# Adafruit_PowerBoost_500C.net
KiCad netlist of a schematic drawn in EAGLE
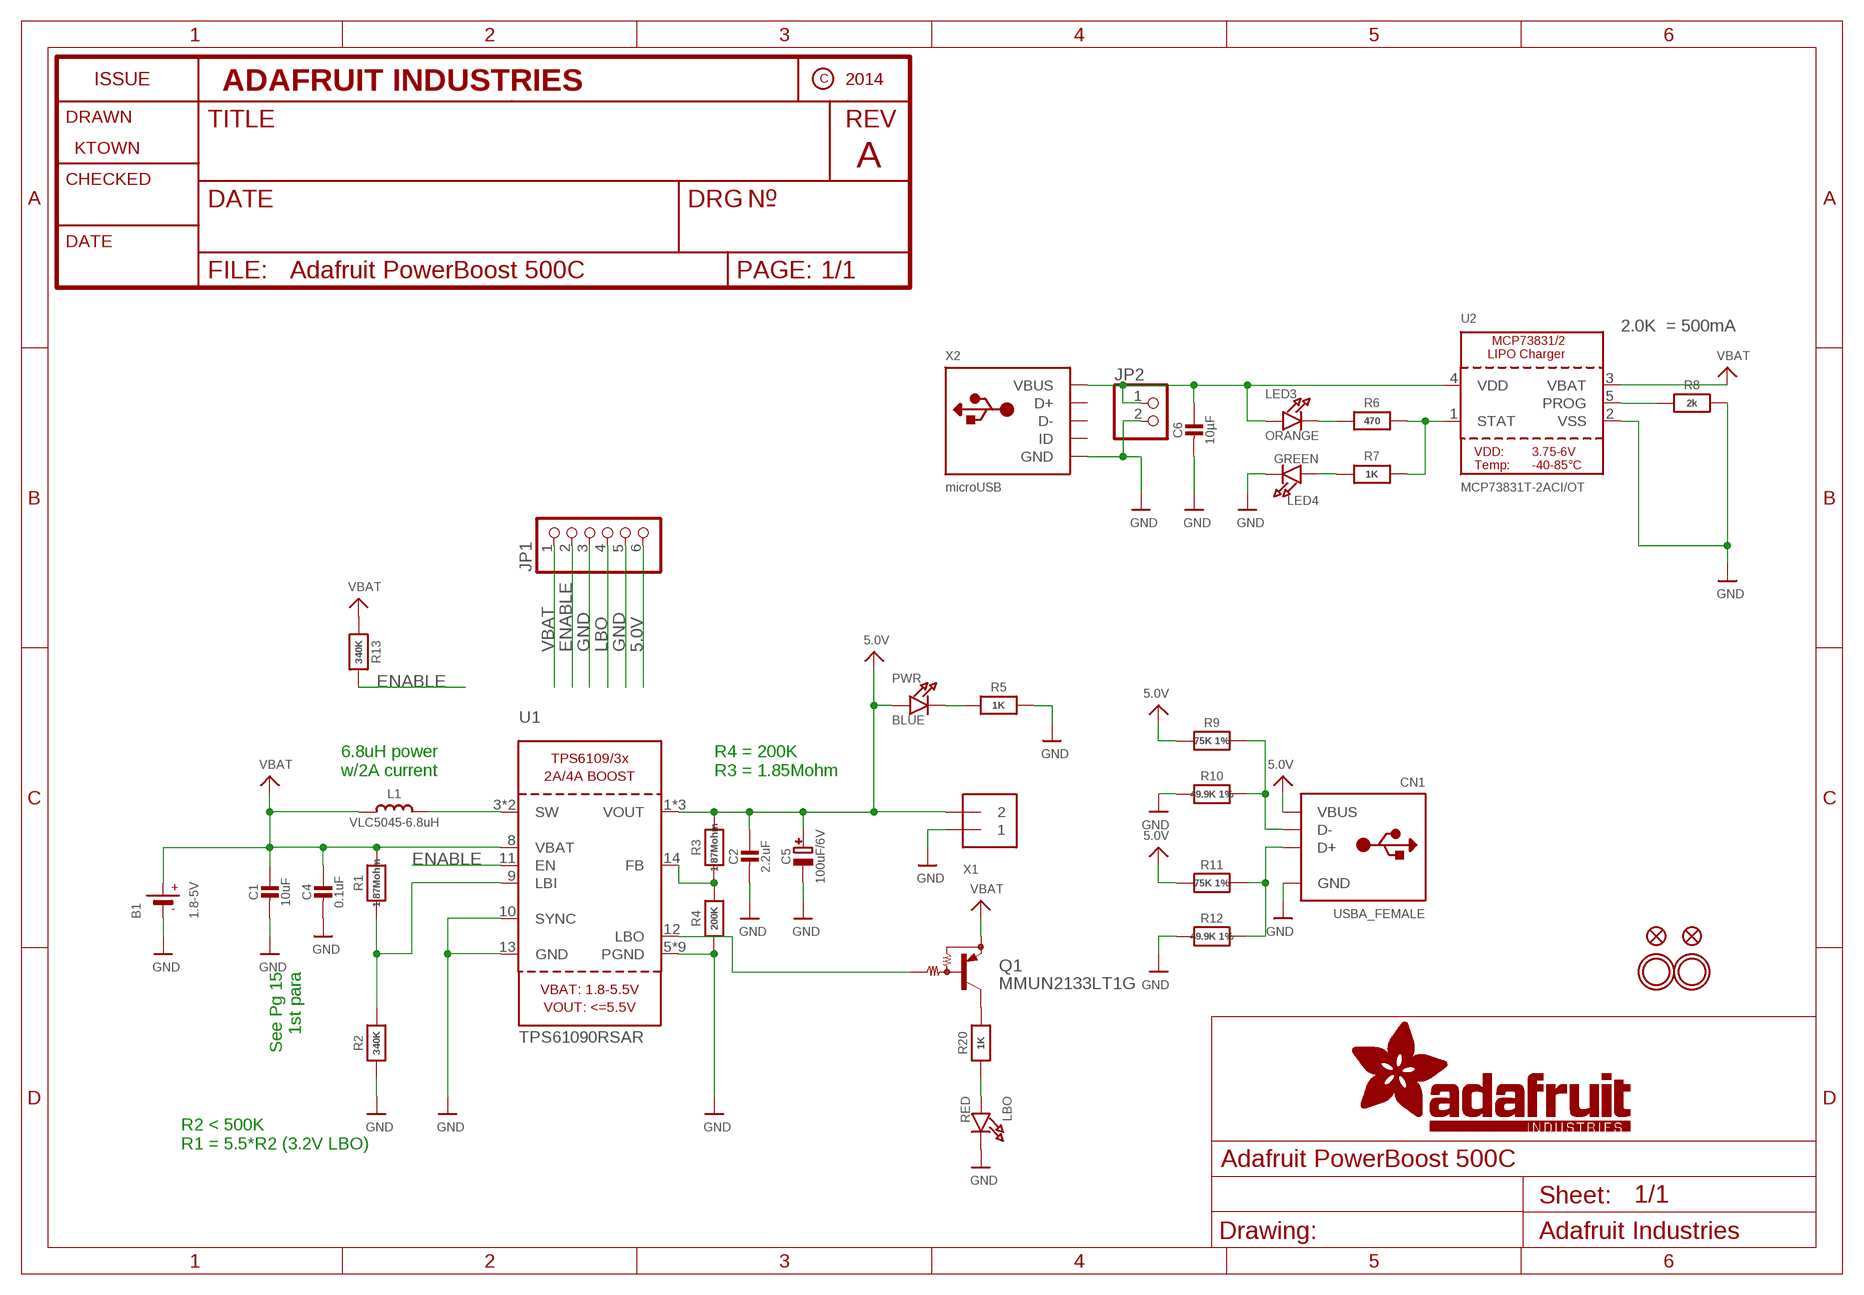
[diagram p0: schematic, sheet 1]

(export (version "E")
  (design (tool "Eeschema 10.0.6"))
  (components
    (comp (ref "B1")
      (value "1.8-5V")
      (footprint "eagle-import:JSTPH2")
      (libsource (lib "eagle-import") (part "BATTERY"))
    )
    (comp (ref "C1")
      (value "10uF")
      (footprint "eagle-import:0805-NO")
      (libsource (lib "eagle-import") (part "CAP_CERAMIC0805-NOOUTLINE"))
    )
    (comp (ref "C2")
      (value "2.2uF")
      (footprint "eagle-import:0805-NO")
      (libsource (lib "eagle-import") (part "CAP_CERAMIC0805-NOOUTLINE"))
    )
    (comp (ref "C4")
      (value "0.1uF")
      (footprint "eagle-import:0805-NO")
      (libsource (lib "eagle-import") (part "CAP_CERAMIC0805-NOOUTLINE"))
    )
    (comp (ref "C5")
      (value "100uF/6V")
      (footprint "eagle-import:EIA3528-21_B-R")
      (libsource (lib "eagle-import") (part "CAP_TANTALUMB/3528_REFLOW"))
    )
    (comp (ref "C6")
      (value "10µF")
      (footprint "eagle-import:0805-NO")
      (libsource (lib "eagle-import") (part "CAP_CERAMIC0805-NOOUTLINE"))
    )
    (comp (ref "CN1")
      (value "USBA_FEMALE")
      (footprint "eagle-import:USB_HOST-PTH")
      (libsource (lib "eagle-import") (part "USB_TYPEAPTHFML"))
    )
    (comp (ref "FID2")
      (value "FIDUCIAL\"\"")
      (footprint "eagle-import:FIDUCIAL_1MM")
      (libsource (lib "eagle-import") (part "FIDUCIAL{dblquote}{dblquote}"))
    )
    (comp (ref "FID3")
      (value "FIDUCIAL\"\"")
      (footprint "eagle-import:FIDUCIAL_1MM")
      (fields (field (name "BOM") "EXCLUDE"))
      (libsource (lib "eagle-import") (part "FIDUCIAL{dblquote}{dblquote}"))
    )
    (comp (ref "JP1")
      (value "PINHD-1X6CB")
      (footprint "eagle-import:1X06-CLEANBIG")
      (libsource (lib "eagle-import") (part "PINHD-1X6CB"))
    )
    (comp (ref "JP2")
      (value "HEADER-1X2ROUND")
      (footprint "eagle-import:1X02_ROUND")
      (libsource (lib "eagle-import") (part "HEADER-1X2ROUND"))
    )
    (comp (ref "L1")
      (value "VLC5045-6.8uH")
      (footprint "eagle-import:INDUCTOR_5X5MM_TDK_VLC5045")
      (libsource (lib "eagle-import") (part "INDUCTORTDK_VLC5045"))
    )
    (comp (ref "LBO")
      (value "RED")
      (footprint "eagle-import:CHIPLED_0805_NOOUTLINE")
      (libsource (lib "eagle-import") (part "LED0805_NOOUTLINE"))
    )
    (comp (ref "LED3")
      (value "ORANGE")
      (footprint "eagle-import:CHIPLED_0805_NOOUTLINE")
      (libsource (lib "eagle-import") (part "LED0805_NOOUTLINE"))
    )
    (comp (ref "LED4")
      (value "GREEN")
      (footprint "eagle-import:CHIPLED_0805_NOOUTLINE")
      (libsource (lib "eagle-import") (part "LED0805_NOOUTLINE"))
    )
    (comp (ref "PWR")
      (value "BLUE")
      (footprint "eagle-import:CHIPLED_0805_NOOUTLINE")
      (libsource (lib "eagle-import") (part "LED0805_NOOUTLINE"))
    )
    (comp (ref "Q1")
      (value "MMUN2133LT1G")
      (footprint "eagle-import:SC59-BEC")
      (libsource (lib "eagle-import") (part "-PNP_DRIVER-SC59-BECMUN2114T1"))
    )
    (comp (ref "R1")
      (value "1.87Mohm")
      (footprint "eagle-import:0805-NO")
      (libsource (lib "eagle-import") (part "RESISTOR0805_NOOUTLINE"))
    )
    (comp (ref "R2")
      (value "340K")
      (footprint "eagle-import:0805-NO")
      (libsource (lib "eagle-import") (part "RESISTOR0805_NOOUTLINE"))
    )
    (comp (ref "R3")
      (value "1.87Mohm")
      (footprint "eagle-import:0805-NO")
      (libsource (lib "eagle-import") (part "RESISTOR0805_NOOUTLINE"))
    )
    (comp (ref "R4")
      (value "200K")
      (footprint "eagle-import:0805-NO")
      (libsource (lib "eagle-import") (part "RESISTOR0805_NOOUTLINE"))
    )
    (comp (ref "R5")
      (value "1K")
      (footprint "eagle-import:0805-NO")
      (libsource (lib "eagle-import") (part "RESISTOR0805_NOOUTLINE"))
    )
    (comp (ref "R6")
      (value "470")
      (footprint "eagle-import:0805-NO")
      (libsource (lib "eagle-import") (part "RESISTOR0805_NOOUTLINE"))
    )
    (comp (ref "R7")
      (value "1K")
      (footprint "eagle-import:0805-NO")
      (libsource (lib "eagle-import") (part "RESISTOR0805_NOOUTLINE"))
    )
    (comp (ref "R8")
      (value "2k")
      (footprint "eagle-import:0805-NO")
      (libsource (lib "eagle-import") (part "RESISTOR0805_NOOUTLINE"))
    )
    (comp (ref "R9")
      (value "75K 1%")
      (footprint "eagle-import:0805-NO")
      (libsource (lib "eagle-import") (part "RESISTOR0805_NOOUTLINE"))
    )
    (comp (ref "R10")
      (value "49.9K 1%")
      (footprint "eagle-import:0805-NO")
      (libsource (lib "eagle-import") (part "RESISTOR0805_NOOUTLINE"))
    )
    (comp (ref "R11")
      (value "75K 1%")
      (footprint "eagle-import:0805-NO")
      (libsource (lib "eagle-import") (part "RESISTOR0805_NOOUTLINE"))
    )
    (comp (ref "R12")
      (value "49.9K 1%")
      (footprint "eagle-import:0805-NO")
      (libsource (lib "eagle-import") (part "RESISTOR0805_NOOUTLINE"))
    )
    (comp (ref "R13")
      (value "340K")
      (footprint "eagle-import:0805-NO")
      (libsource (lib "eagle-import") (part "RESISTOR0805_NOOUTLINE"))
    )
    (comp (ref "R20")
      (value "1K")
      (footprint "eagle-import:0805-NO")
      (libsource (lib "eagle-import") (part "RESISTOR0805_NOOUTLINE"))
    )
    (comp (ref "U$10")
      (value "MOUNTINGHOLE2.5")
      (footprint "eagle-import:MOUNTINGHOLE_2.5_PLATED")
      (libsource (lib "eagle-import") (part "MOUNTINGHOLE2.5"))
    )
    (comp (ref "U$12")
      (value "MOUNTINGHOLE2.5")
      (footprint "eagle-import:MOUNTINGHOLE_2.5_PLATED")
      (libsource (lib "eagle-import") (part "MOUNTINGHOLE2.5"))
    )
    (comp (ref "U1")
      (value "TPS61090RSAR")
      (footprint "eagle-import:PVQFN-16")
      (libsource (lib "eagle-import") (part "VREG_TPS6103X"))
    )
    (comp (ref "U2")
      (value "MCP73831T-2ACI/OT")
      (footprint "eagle-import:SOT23-5")
      (libsource (lib "eagle-import") (part "MCP73831/2"))
    )
    (comp (ref "X1")
      (value "TERMBLOCK_1X2")
      (footprint "eagle-import:TERMBLOCK_1X2-3.5MM")
      (libsource (lib "eagle-import") (part "TERMBLOCK_1X2"))
    )
    (comp (ref "X2")
      (value "microUSB")
      (footprint "eagle-import:4UCONN_20329")
      (libsource (lib "eagle-import") (part "USBMICRO_20329"))
    )
  )
  (nets
    (net (code "1") (name "/ENABLE") (class "Default")
      (node (ref "JP1") (pin "2") (pinfunction "2_2") (pintype "passive"))
      (node (ref "R13") (pin "2") (pinfunction "2_2") (pintype "passive"))
      (node (ref "U1") (pin "11") (pinfunction "EN_11") (pintype "input"))
    )
    (net (code "2") (name "/LBO") (class "Default")
      (node (ref "JP1") (pin "4") (pinfunction "4_4") (pintype "passive"))
      (node (ref "Q1") (pin "B") (pinfunction "B_B") (pintype "passive"))
      (node (ref "U1") (pin "12") (pinfunction "LBO_12") (pintype "output"))
    )
    (net (code "3") (name "5.0V") (class "Default")
      (node (ref "C2") (pin "1") (pinfunction "1_1") (pintype "passive"))
      (node (ref "C5") (pin "+") (pinfunction "+_+") (pintype "passive"))
      (node (ref "CN1") (pin "VBUS") (pinfunction "VBUS_VBUS") (pintype "power_in"))
      (node (ref "JP1") (pin "6") (pinfunction "6_6") (pintype "passive"))
      (node (ref "PWR") (pin "A") (pinfunction "A_A") (pintype "passive"))
      (node (ref "R11") (pin "2") (pinfunction "2_2") (pintype "passive"))
      (node (ref "R3") (pin "2") (pinfunction "2_2") (pintype "passive"))
      (node (ref "R9") (pin "2") (pinfunction "2_2") (pintype "passive"))
      (node (ref "U1") (pin "1") (pinfunction "VOUT_1") (pintype "power_in"))
      (node (ref "U1") (pin "15") (pinfunction "VOUT_15") (pintype "power_in"))
      (node (ref "U1") (pin "16") (pinfunction "VOUT_16") (pintype "power_in"))
      (node (ref "X1") (pin "2") (pinfunction "2_2") (pintype "passive"))
    )
    (net (code "4") (name "GND") (class "Default")
      (node (ref "B1") (pin "1") (pinfunction "-_1") (pintype "passive"))
      (node (ref "C1") (pin "2") (pinfunction "2_2") (pintype "passive"))
      (node (ref "C2") (pin "2") (pinfunction "2_2") (pintype "passive"))
      (node (ref "C4") (pin "2") (pinfunction "2_2") (pintype "passive"))
      (node (ref "C5") (pin "-") (pinfunction "-_-") (pintype "passive"))
      (node (ref "C6") (pin "2") (pinfunction "2_2") (pintype "passive"))
      (node (ref "CN1") (pin "GND") (pinfunction "GND_GND") (pintype "power_in"))
      (node (ref "JP1") (pin "3") (pinfunction "3_3") (pintype "passive"))
      (node (ref "JP1") (pin "5") (pinfunction "5_5") (pintype "passive"))
      (node (ref "JP2") (pin "2") (pinfunction "2_2") (pintype "passive"))
      (node (ref "LBO") (pin "C") (pinfunction "C_C") (pintype "passive"))
      (node (ref "LED4") (pin "C") (pinfunction "C_C") (pintype "passive"))
      (node (ref "R10") (pin "2") (pinfunction "2_2") (pintype "passive"))
      (node (ref "R12") (pin "2") (pinfunction "2_2") (pintype "passive"))
      (node (ref "R2") (pin "1") (pinfunction "1_1") (pintype "passive"))
      (node (ref "R4") (pin "1") (pinfunction "1_1") (pintype "passive"))
      (node (ref "R5") (pin "2") (pinfunction "2_2") (pintype "passive"))
      (node (ref "R8") (pin "2") (pinfunction "2_2") (pintype "passive"))
      (node (ref "U1") (pin "10") (pinfunction "SYNC_10") (pintype "input"))
      (node (ref "U1") (pin "13") (pinfunction "GND_13") (pintype "power_in"))
      (node (ref "U1") (pin "5") (pinfunction "PGND_5") (pintype "power_in"))
      (node (ref "U1") (pin "6") (pinfunction "PGND_6") (pintype "power_in"))
      (node (ref "U1") (pin "7") (pinfunction "PGND_7") (pintype "power_in"))
      (node (ref "U1") (pin "P$18") (pinfunction "PGND_P$18") (pintype "power_in"))
      (node (ref "U1") (pin "P$19") (pinfunction "PGND_P$19") (pintype "power_in"))
      (node (ref "U1") (pin "P$20") (pinfunction "PGND_P$20") (pintype "power_in"))
      (node (ref "U1") (pin "P$21") (pinfunction "PGND_P$21") (pintype "power_in"))
      (node (ref "U1") (pin "P$22") (pinfunction "PGND_P$22") (pintype "power_in"))
      (node (ref "U1") (pin "THERMAL") (pinfunction "PGND_THERMAL") (pintype "power_in"))
      (node (ref "U2") (pin "2") (pinfunction "VSS_2") (pintype "power_in"))
      (node (ref "X1") (pin "1") (pinfunction "1_1") (pintype "passive"))
      (node (ref "X2") (pin "BASE@1") (pinfunction "GND_BASE@1") (pintype "power_in"))
      (node (ref "X2") (pin "BASE@2") (pinfunction "GND_BASE@2") (pintype "power_in"))
      (node (ref "X2") (pin "GND") (pinfunction "GND_GND") (pintype "power_in"))
      (node (ref "X2") (pin "SPRT@1") (pinfunction "GND_SPRT@1") (pintype "power_in"))
      (node (ref "X2") (pin "SPRT@2") (pinfunction "GND_SPRT@2") (pintype "power_in"))
      (node (ref "X2") (pin "SPRT@3") (pinfunction "GND_SPRT@3") (pintype "power_in"))
      (node (ref "X2") (pin "SPRT@4") (pinfunction "GND_SPRT@4") (pintype "power_in"))
    )
    (net (code "5") (name "Net-(CN1-PadD+)") (class "Default")
      (node (ref "CN1") (pin "D+") (pinfunction "D+_D+") (pintype "bidirectional"))
      (node (ref "R11") (pin "1") (pinfunction "1_1") (pintype "passive"))
      (node (ref "R12") (pin "1") (pinfunction "1_1") (pintype "passive"))
    )
    (net (code "6") (name "Net-(CN1-PadD-)") (class "Default")
      (node (ref "CN1") (pin "D-") (pinfunction "D-_D-") (pintype "bidirectional"))
      (node (ref "R10") (pin "1") (pinfunction "1_1") (pintype "passive"))
      (node (ref "R9") (pin "1") (pinfunction "1_1") (pintype "passive"))
    )
    (net (code "7") (name "Net-(L1-2)") (class "Default")
      (node (ref "L1") (pin "P$2") (pinfunction "2_P$2") (pintype "passive"))
      (node (ref "U1") (pin "3") (pinfunction "SW_3") (pintype "input"))
      (node (ref "U1") (pin "4") (pinfunction "SW_4") (pintype "input"))
    )
    (net (code "8") (name "Net-(LBO-PadA)") (class "Default")
      (node (ref "LBO") (pin "A") (pinfunction "A_A") (pintype "passive"))
      (node (ref "R20") (pin "1") (pinfunction "1_1") (pintype "passive"))
    )
    (net (code "9") (name "Net-(LED3-PadC)") (class "Default")
      (node (ref "LED3") (pin "C") (pinfunction "C_C") (pintype "passive"))
      (node (ref "R6") (pin "1") (pinfunction "1_1") (pintype "passive"))
    )
    (net (code "10") (name "Net-(LED4-PadA)") (class "Default")
      (node (ref "LED4") (pin "A") (pinfunction "A_A") (pintype "passive"))
      (node (ref "R7") (pin "1") (pinfunction "1_1") (pintype "passive"))
    )
    (net (code "11") (name "Net-(PWR-PadC)") (class "Default")
      (node (ref "PWR") (pin "C") (pinfunction "C_C") (pintype "passive"))
      (node (ref "R5") (pin "1") (pinfunction "1_1") (pintype "passive"))
    )
    (net (code "12") (name "Net-(Q1-PadC)") (class "Default")
      (node (ref "Q1") (pin "C") (pinfunction "C_C") (pintype "passive"))
      (node (ref "R20") (pin "2") (pinfunction "2_2") (pintype "passive"))
    )
    (net (code "13") (name "Net-(U1-FB)") (class "Default")
      (node (ref "R3") (pin "1") (pinfunction "1_1") (pintype "passive"))
      (node (ref "R4") (pin "2") (pinfunction "2_2") (pintype "passive"))
      (node (ref "U1") (pin "14") (pinfunction "FB_14") (pintype "input"))
    )
    (net (code "14") (name "Net-(U1-LBI)") (class "Default")
      (node (ref "R1") (pin "1") (pinfunction "1_1") (pintype "passive"))
      (node (ref "R2") (pin "2") (pinfunction "2_2") (pintype "passive"))
      (node (ref "U1") (pin "9") (pinfunction "LBI_9") (pintype "input"))
    )
    (net (code "15") (name "Net-(U2-PROG)") (class "Default")
      (node (ref "R8") (pin "1") (pinfunction "1_1") (pintype "passive"))
      (node (ref "U2") (pin "5") (pinfunction "PROG_5") (pintype "input"))
    )
    (net (code "16") (name "Net-(U2-STAT)") (class "Default")
      (node (ref "R6") (pin "2") (pinfunction "2_2") (pintype "passive"))
      (node (ref "R7") (pin "2") (pinfunction "2_2") (pintype "passive"))
      (node (ref "U2") (pin "1") (pinfunction "STAT_1") (pintype "output"))
    )
    (net (code "17") (name "Net-(U2-VDD)") (class "Default")
      (node (ref "C6") (pin "1") (pinfunction "1_1") (pintype "passive"))
      (node (ref "JP2") (pin "1") (pinfunction "1_1") (pintype "passive"))
      (node (ref "LED3") (pin "A") (pinfunction "A_A") (pintype "passive"))
      (node (ref "U2") (pin "4") (pinfunction "VDD_4") (pintype "power_in"))
      (node (ref "X2") (pin "VBUS") (pinfunction "VBUS_VBUS") (pintype "power_in"))
    )
    (net (code "18") (name "VBAT") (class "Default")
      (node (ref "B1") (pin "2") (pinfunction "+_2") (pintype "passive"))
      (node (ref "C1") (pin "1") (pinfunction "1_1") (pintype "passive"))
      (node (ref "C4") (pin "1") (pinfunction "1_1") (pintype "passive"))
      (node (ref "JP1") (pin "1") (pinfunction "1_1") (pintype "passive"))
      (node (ref "L1") (pin "P$1") (pinfunction "1_P$1") (pintype "passive"))
      (node (ref "Q1") (pin "E") (pinfunction "E_E") (pintype "passive"))
      (node (ref "R1") (pin "2") (pinfunction "2_2") (pintype "passive"))
      (node (ref "R13") (pin "1") (pinfunction "1_1") (pintype "passive"))
      (node (ref "U1") (pin "8") (pinfunction "VBAT_8") (pintype "input"))
      (node (ref "U2") (pin "3") (pinfunction "VBAT_3") (pintype "power_in"))
    )
    (net (code "19") (name "unconnected-(X2-PadD+)") (class "Default")
      (node (ref "X2") (pin "D+") (pinfunction "D+_D+") (pintype "bidirectional"))
    )
    (net (code "20") (name "unconnected-(X2-PadD-)") (class "Default")
      (node (ref "X2") (pin "D-") (pinfunction "D-_D-") (pintype "bidirectional"))
    )
    (net (code "21") (name "unconnected-(X2-PadID)") (class "Default")
      (node (ref "X2") (pin "ID") (pinfunction "ID_ID") (pintype "bidirectional"))
    )
  )
)
